# USB_Communication_Sheet.net
KiCad netlist of a schematic drawn in Altium Designer
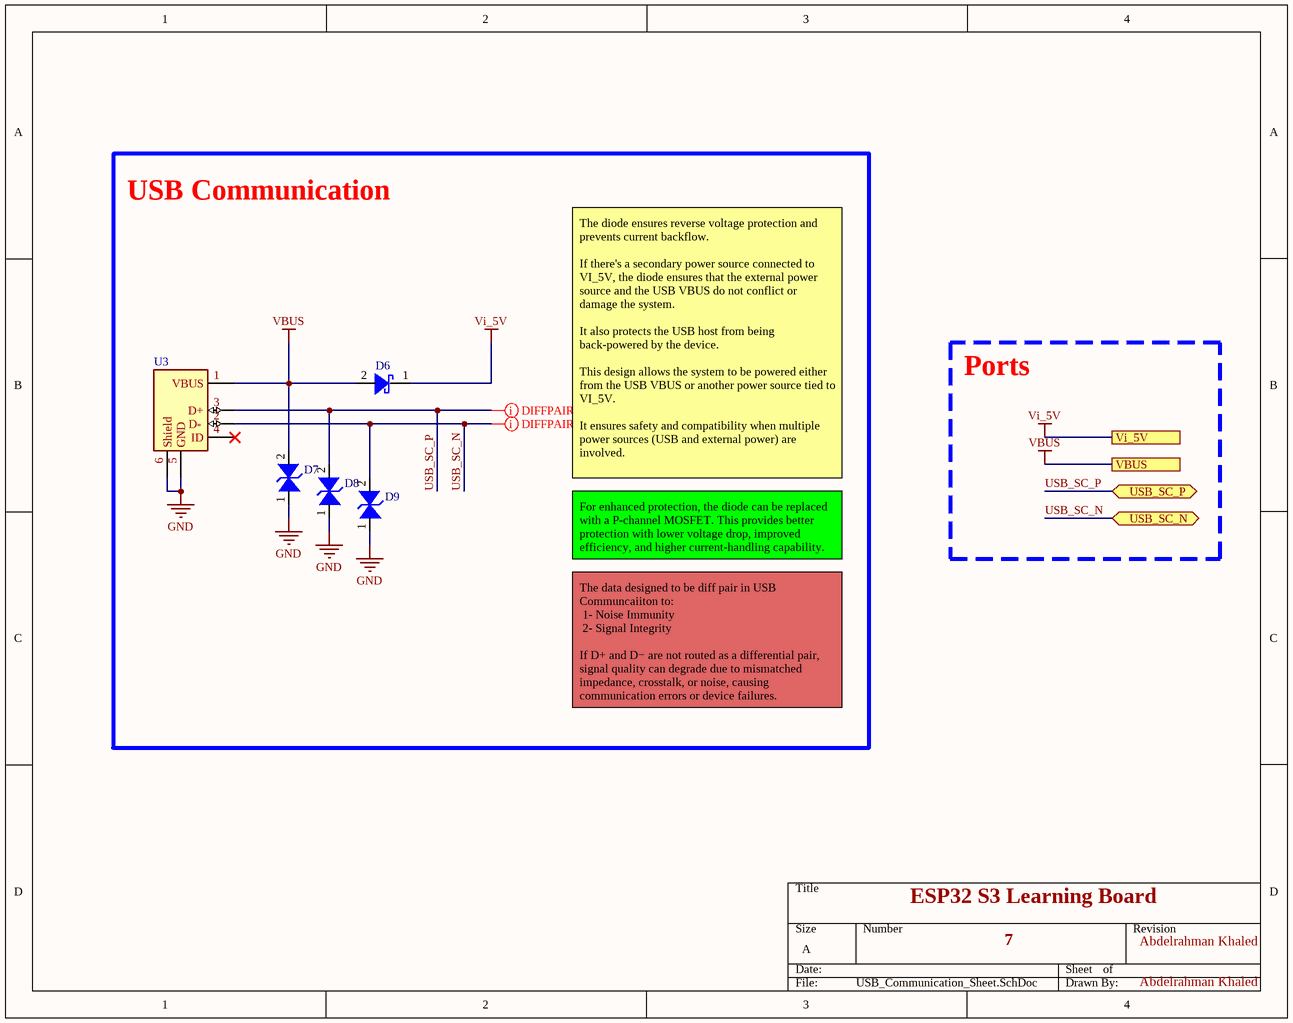
[diagram p0: USB_Communication_Sheet.SchDoc]

(export (version "E")
  (design (tool "Eeschema 10.0.6"))
  (components
    (comp (ref "D6")
      (value "0.2V Drop Volt")
      (footprint "Schoktty Diode")
      (description "NRVB120ESFT1G")
      (libsource (lib "ESP32_S3_Integrated_Library") (part "Schottky Diode"))
    )
    (comp (ref "D7")
      (value "TVS Diode")
      (footprint "TVS Diode")
      (libsource (lib "ESP32_S3_Integrated_Library") (part "TVS Diode"))
    )
    (comp (ref "D8")
      (value "TVS Diode")
      (footprint "TVS Diode")
      (libsource (lib "ESP32_S3_Integrated_Library") (part "TVS Diode"))
    )
    (comp (ref "D9")
      (value "TVS Diode")
      (footprint "TVS Diode")
      (libsource (lib "ESP32_S3_Integrated_Library") (part "TVS Diode"))
    )
    (comp (ref "U3")
      (value "USB_B Micro")
      (footprint "USB8_Micro")
      (libsource (lib "ESP32_S3_Integrated_Library") (part "USB_B Micro"))
    )
  )
  (nets
    (net (code "1") (name "/USB_SC_N") (class "Default")
      (node (ref "D9") (pin "2") (pintype "passive"))
      (node (ref "U3") (pin "2") (pinfunction "D-_2") (pintype "bidirectional"))
    )
    (net (code "2") (name "/USB_SC_P") (class "Default")
      (node (ref "D8") (pin "2") (pintype "passive"))
      (node (ref "U3") (pin "3") (pinfunction "D+_3") (pintype "bidirectional"))
    )
    (net (code "3") (name "GND") (class "Default")
      (node (ref "D7") (pin "1") (pintype "passive"))
      (node (ref "D8") (pin "1") (pintype "passive"))
      (node (ref "D9") (pin "1") (pintype "passive"))
      (node (ref "U3") (pin "5") (pinfunction "GND_5") (pintype "power_in"))
      (node (ref "U3") (pin "6") (pinfunction "Shield_6") (pintype "power_in"))
    )
    (net (code "4") (name "VBUS") (class "Default")
      (node (ref "D6") (pin "2") (pintype "passive"))
      (node (ref "D7") (pin "2") (pintype "passive"))
      (node (ref "U3") (pin "1") (pinfunction "VBUS_1") (pintype "power_in"))
    )
    (net (code "5") (name "Vi_5V") (class "Default") (node (ref "D6") (pin "1") (pintype "passive")))
    (net (code "6") (name "unconnected-(U3-ID-Pad4)") (class "Default")
      (node (ref "U3") (pin "4") (pinfunction "ID_4") (pintype "passive+no_connect"))
    )
  )
)
